# START_JUMPER.net
KiCad netlist of a schematic drawn in Altium Designer
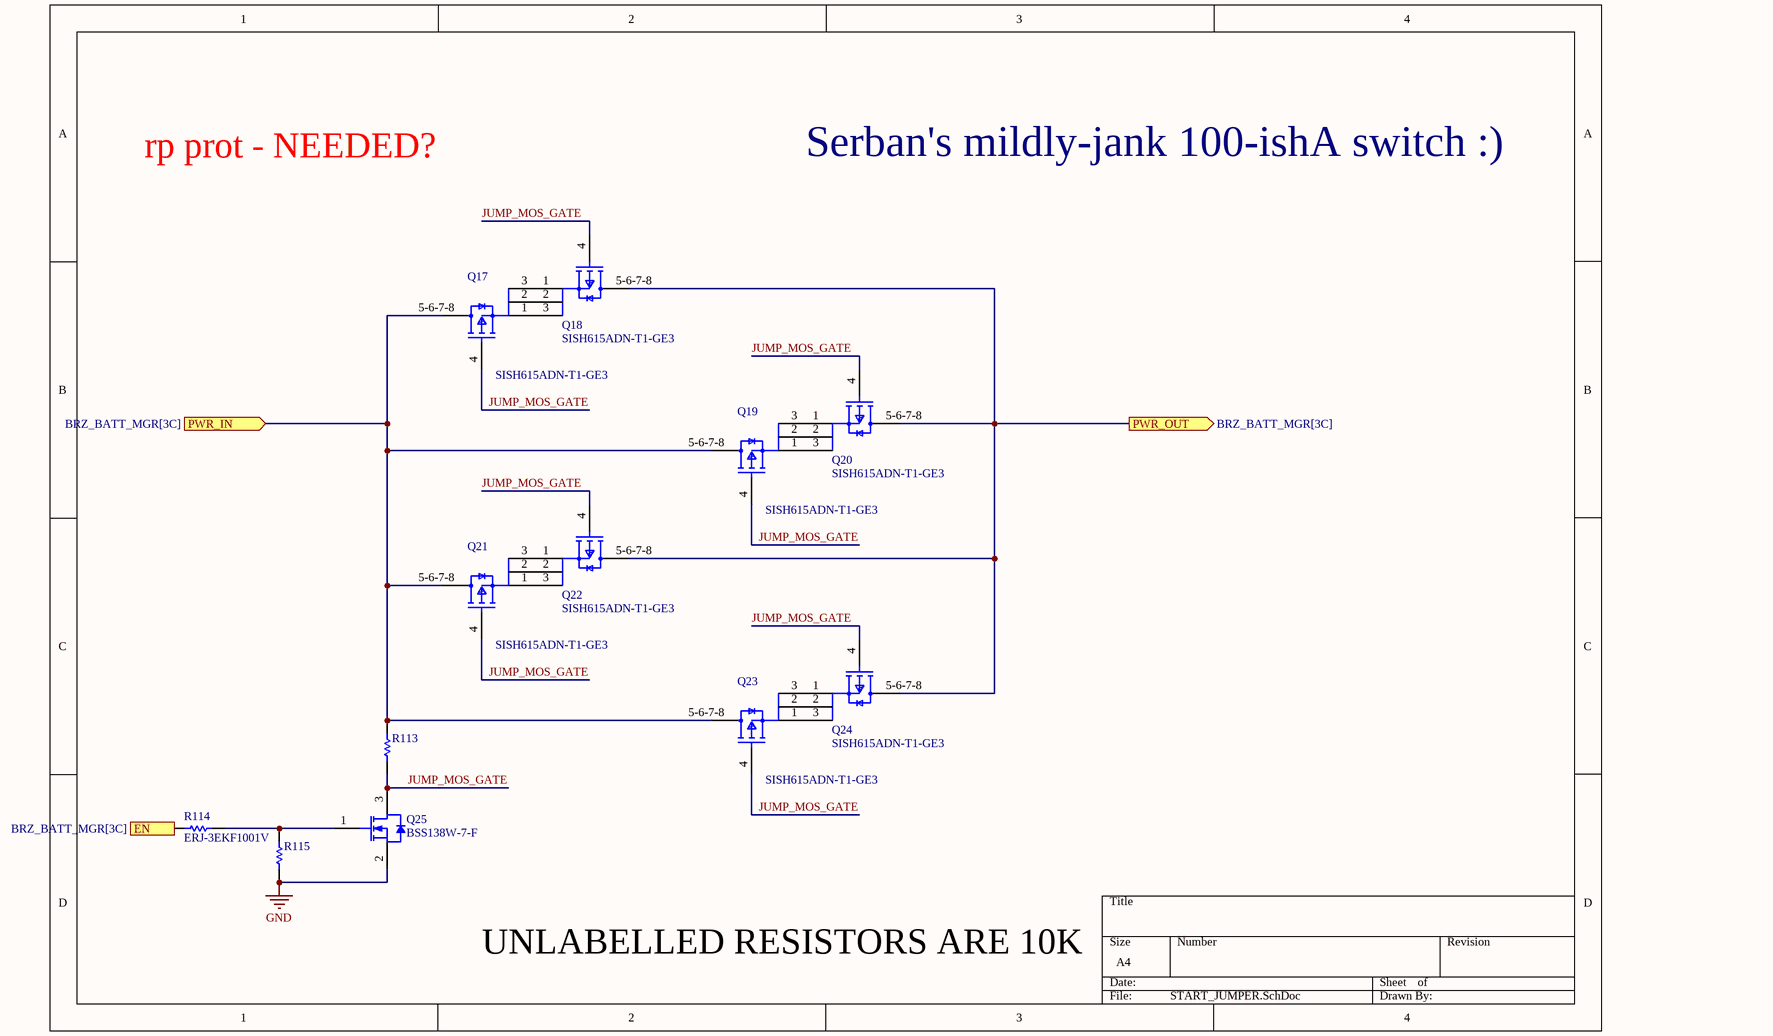
[diagram p0: START_JUMPER.SchDoc]

(export (version "E")
  (design (tool "Eeschema 10.0.6"))
  (components
    (comp (ref "Q17")
      (value "SISH615ADN-T1-GE3")
      (footprint "SISH615ADN-T1-GE3-Footprint-1")
      (description "Trans MOSFET P-CH 20V 22.1A 8-Pin PowerPAK 1212 EP T/R")
      (libsource (lib "uORocketry Hardware") (part "SISH615ADN-T1-GE3-Symbol-1"))
    )
    (comp (ref "Q18")
      (value "SISH615ADN-T1-GE3")
      (footprint "SISH615ADN-T1-GE3-Footprint-1")
      (description "Trans MOSFET P-CH 20V 22.1A 8-Pin PowerPAK 1212 EP T/R")
      (libsource (lib "uORocketry Hardware") (part "SISH615ADN-T1-GE3-Symbol-1"))
    )
    (comp (ref "Q19")
      (value "SISH615ADN-T1-GE3")
      (footprint "SISH615ADN-T1-GE3-Footprint-1")
      (description "Trans MOSFET P-CH 20V 22.1A 8-Pin PowerPAK 1212 EP T/R")
      (libsource (lib "uORocketry Hardware") (part "SISH615ADN-T1-GE3-Symbol-1"))
    )
    (comp (ref "Q20")
      (value "SISH615ADN-T1-GE3")
      (footprint "SISH615ADN-T1-GE3-Footprint-1")
      (description "Trans MOSFET P-CH 20V 22.1A 8-Pin PowerPAK 1212 EP T/R")
      (libsource (lib "uORocketry Hardware") (part "SISH615ADN-T1-GE3-Symbol-1"))
    )
    (comp (ref "Q21")
      (value "SISH615ADN-T1-GE3")
      (footprint "SISH615ADN-T1-GE3-Footprint-1")
      (description "Trans MOSFET P-CH 20V 22.1A 8-Pin PowerPAK 1212 EP T/R")
      (libsource (lib "uORocketry Hardware") (part "SISH615ADN-T1-GE3-Symbol-1"))
    )
    (comp (ref "Q22")
      (value "SISH615ADN-T1-GE3")
      (footprint "SISH615ADN-T1-GE3-Footprint-1")
      (description "Trans MOSFET P-CH 20V 22.1A 8-Pin PowerPAK 1212 EP T/R")
      (libsource (lib "uORocketry Hardware") (part "SISH615ADN-T1-GE3-Symbol-1"))
    )
    (comp (ref "Q23")
      (value "SISH615ADN-T1-GE3")
      (footprint "SISH615ADN-T1-GE3-Footprint-1")
      (description "Trans MOSFET P-CH 20V 22.1A 8-Pin PowerPAK 1212 EP T/R")
      (libsource (lib "uORocketry Hardware") (part "SISH615ADN-T1-GE3-Symbol-1"))
    )
    (comp (ref "Q24")
      (value "SISH615ADN-T1-GE3")
      (footprint "SISH615ADN-T1-GE3-Footprint-1")
      (description "Trans MOSFET P-CH 20V 22.1A 8-Pin PowerPAK 1212 EP T/R")
      (libsource (lib "uORocketry Hardware") (part "SISH615ADN-T1-GE3-Symbol-1"))
    )
    (comp (ref "Q25")
      (value "BSS138W-7-F")
      (footprint "DIOD-SOT323-3_V")
      (fields (field (name "MANUFACTURER") "DiodesIncorporated"))
      (libsource (lib "Altium Content Vault") (part "NEMOS-GSD-3"))
    )
    (comp (ref "R113")
      (value "ERJ3EKF1002V")
      (footprint "RESC1609X55X30LL15T15")
      (description "Chip Resistor, 10 KOhm, +/- 1%, 0.1 W, -55 to 155 degC, 0603 (1608 Metric), RoHS, Tape and Reel")
      (fields (field (name "TOLERANCE") "1%") (field (name "MANUFACTURER") "Panasonic"))
      (libsource (lib "Altium Content Vault") (part "RES-2"))
    )
    (comp (ref "R114")
      (value "ERJ-3EKF1001V")
      (footprint "RESC1608X55X30LL15T15")
      (fields (field (name "MANUFACTURER") "Panasonic"))
      (libsource (lib "Altium Content Vault") (part "RES"))
    )
    (comp (ref "R115")
      (value "ERJ3EKF1002V")
      (footprint "RESC1609X55X30LL15T15")
      (description "Chip Resistor, 10 KOhm, +/- 1%, 0.1 W, -55 to 155 degC, 0603 (1608 Metric), RoHS, Tape and Reel")
      (fields (field (name "TOLERANCE") "1%") (field (name "MANUFACTURER") "Panasonic"))
      (libsource (lib "Altium Content Vault") (part "RES-2"))
    )
  )
  (nets
    (net (code "2") (name "/JUMP_MOS_GATE") (class "Default")
      (node (ref "Q17") (pin "4") (pinfunction "G_4") (pintype "passive"))
      (node (ref "Q18") (pin "4") (pinfunction "G_4") (pintype "passive"))
      (node (ref "Q19") (pin "4") (pinfunction "G_4") (pintype "passive"))
      (node (ref "Q20") (pin "4") (pinfunction "G_4") (pintype "passive"))
      (node (ref "Q21") (pin "4") (pinfunction "G_4") (pintype "passive"))
      (node (ref "Q22") (pin "4") (pinfunction "G_4") (pintype "passive"))
      (node (ref "Q23") (pin "4") (pinfunction "G_4") (pintype "passive"))
      (node (ref "Q24") (pin "4") (pinfunction "G_4") (pintype "passive"))
      (node (ref "Q25") (pin "3") (pinfunction "D_3") (pintype "passive"))
      (node (ref "R113") (pin "1") (pinfunction "1_1") (pintype "passive"))
    )
    (net (code "3") (name "/PWR_IN") (class "Default")
      (node (ref "Q17") (pin "5-6-7-8") (pinfunction "D_5-6-7-8") (pintype "passive"))
      (node (ref "Q19") (pin "5-6-7-8") (pinfunction "D_5-6-7-8") (pintype "passive"))
      (node (ref "Q21") (pin "5-6-7-8") (pinfunction "D_5-6-7-8") (pintype "passive"))
      (node (ref "Q23") (pin "5-6-7-8") (pinfunction "D_5-6-7-8") (pintype "passive"))
      (node (ref "R113") (pin "2") (pinfunction "2_2") (pintype "passive"))
    )
    (net (code "4") (name "/PWR_OUT") (class "Default")
      (node (ref "Q18") (pin "5-6-7-8") (pinfunction "D_5-6-7-8") (pintype "passive"))
      (node (ref "Q20") (pin "5-6-7-8") (pinfunction "D_5-6-7-8") (pintype "passive"))
      (node (ref "Q22") (pin "5-6-7-8") (pinfunction "D_5-6-7-8") (pintype "passive"))
      (node (ref "Q24") (pin "5-6-7-8") (pinfunction "D_5-6-7-8") (pintype "passive"))
    )
    (net (code "5") (name "GND") (class "Default")
      (node (ref "Q25") (pin "2") (pinfunction "S_2") (pintype "passive"))
      (node (ref "R115") (pin "1") (pinfunction "1_1") (pintype "passive"))
    )
    (net (code "6") (name "Net-(Q17-S-Pad1)") (class "Default")
      (node (ref "Q17") (pin "1") (pinfunction "S_1") (pintype "passive"))
      (node (ref "Q18") (pin "3") (pinfunction "S_3") (pintype "passive"))
    )
    (net (code "7") (name "Net-(Q17-S-Pad2)") (class "Default")
      (node (ref "Q17") (pin "2") (pinfunction "S_2") (pintype "passive"))
      (node (ref "Q18") (pin "2") (pinfunction "S_2") (pintype "passive"))
    )
    (net (code "8") (name "Net-(Q17-S-Pad3)") (class "Default")
      (node (ref "Q17") (pin "3") (pinfunction "S_3") (pintype "passive"))
      (node (ref "Q18") (pin "1") (pinfunction "S_1") (pintype "passive"))
    )
    (net (code "9") (name "Net-(Q19-S-Pad1)") (class "Default")
      (node (ref "Q19") (pin "1") (pinfunction "S_1") (pintype "passive"))
      (node (ref "Q20") (pin "3") (pinfunction "S_3") (pintype "passive"))
    )
    (net (code "10") (name "Net-(Q19-S-Pad2)") (class "Default")
      (node (ref "Q19") (pin "2") (pinfunction "S_2") (pintype "passive"))
      (node (ref "Q20") (pin "2") (pinfunction "S_2") (pintype "passive"))
    )
    (net (code "11") (name "Net-(Q19-S-Pad3)") (class "Default")
      (node (ref "Q19") (pin "3") (pinfunction "S_3") (pintype "passive"))
      (node (ref "Q20") (pin "1") (pinfunction "S_1") (pintype "passive"))
    )
    (net (code "12") (name "Net-(Q21-S-Pad1)") (class "Default")
      (node (ref "Q21") (pin "1") (pinfunction "S_1") (pintype "passive"))
      (node (ref "Q22") (pin "3") (pinfunction "S_3") (pintype "passive"))
    )
    (net (code "13") (name "Net-(Q21-S-Pad2)") (class "Default")
      (node (ref "Q21") (pin "2") (pinfunction "S_2") (pintype "passive"))
      (node (ref "Q22") (pin "2") (pinfunction "S_2") (pintype "passive"))
    )
    (net (code "14") (name "Net-(Q21-S-Pad3)") (class "Default")
      (node (ref "Q21") (pin "3") (pinfunction "S_3") (pintype "passive"))
      (node (ref "Q22") (pin "1") (pinfunction "S_1") (pintype "passive"))
    )
    (net (code "15") (name "Net-(Q23-S-Pad1)") (class "Default")
      (node (ref "Q23") (pin "1") (pinfunction "S_1") (pintype "passive"))
      (node (ref "Q24") (pin "3") (pinfunction "S_3") (pintype "passive"))
    )
    (net (code "16") (name "Net-(Q23-S-Pad2)") (class "Default")
      (node (ref "Q23") (pin "2") (pinfunction "S_2") (pintype "passive"))
      (node (ref "Q24") (pin "2") (pinfunction "S_2") (pintype "passive"))
    )
    (net (code "17") (name "Net-(Q23-S-Pad3)") (class "Default")
      (node (ref "Q23") (pin "3") (pinfunction "S_3") (pintype "passive"))
      (node (ref "Q24") (pin "1") (pinfunction "S_1") (pintype "passive"))
    )
    (net (code "18") (name "Net-(Q25-G)") (class "Default")
      (node (ref "Q25") (pin "1") (pinfunction "G_1") (pintype "passive"))
      (node (ref "R114") (pin "1") (pinfunction "1_1") (pintype "passive"))
      (node (ref "R115") (pin "2") (pinfunction "2_2") (pintype "passive"))
    )
    (net (code "19") (name "unconnected-(R114-Pad2)") (class "Default")
      (node (ref "R114") (pin "2") (pinfunction "2_2") (pintype "passive"))
    )
  )
)
